# DisplaySupplies.net
KiCad netlist of a schematic drawn in Altium Designer
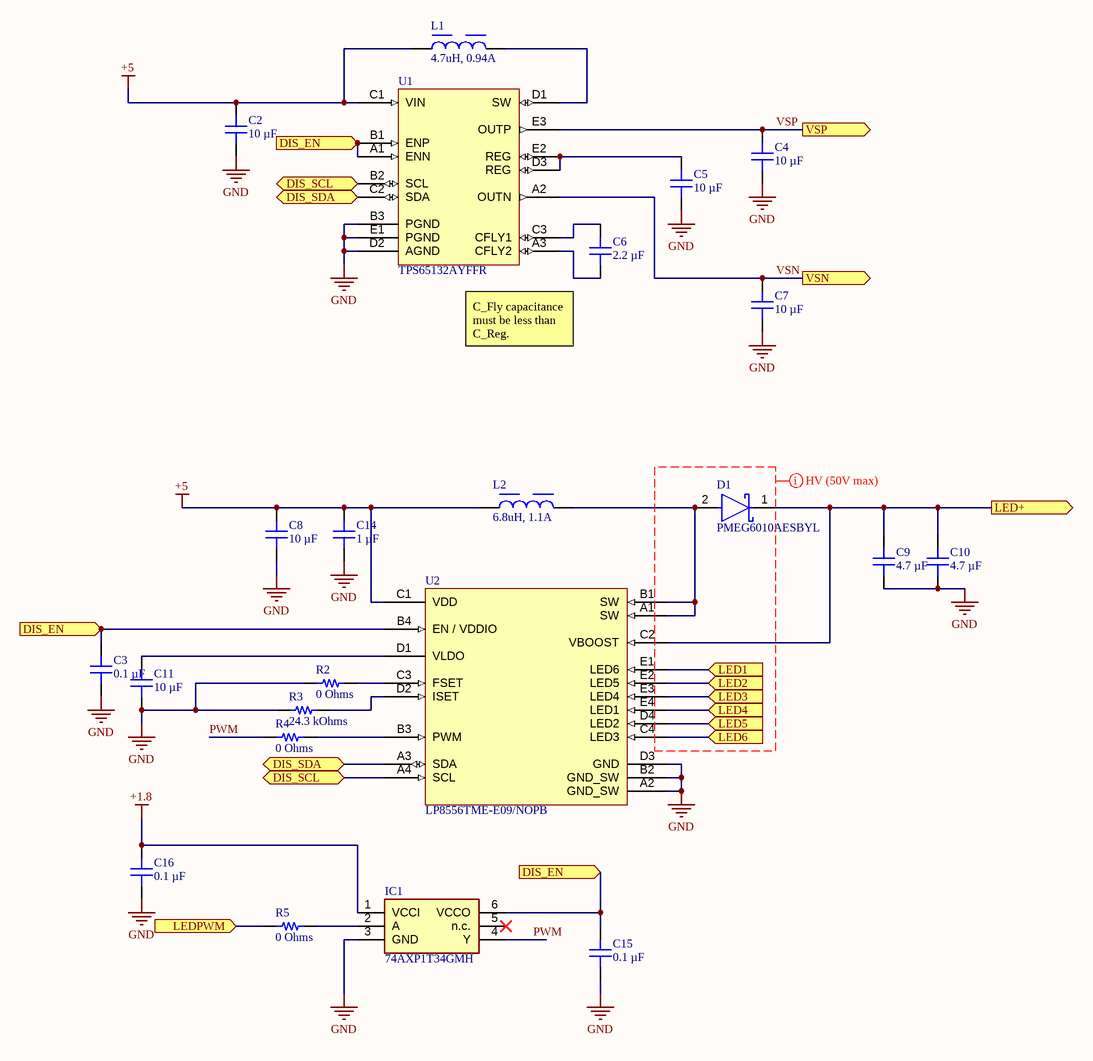
[diagram p0: DisplaySupplies.SchDoc]

(export (version "E")
  (design (tool "Eeschema 10.0.6"))
  (components
    (comp (ref "C2")
      (value "10 µF")
      (footprint "CAP 0603_1608")
      (description "CAP CER 10UF 16V X5R 0603")
      (fields
        (field (name "PART NUMBER") "GRM188R61C106MA73D")
        (field (name "MANUFACTURER") "Murata Electronics")
      )
      (libsource (lib "Celestial Altium Library - altium_library") (part "Capacitor"))
    )
    (comp (ref "C3")
      (value "0.1 µF")
      (footprint "CAP 0201_0603")
      (description "CAP CER 0.1UF 10V X5R 0201")
      (fields
        (field (name "PART NUMBER") "GRM033R61A104KE15D")
        (field (name "MANUFACTURER") "Murata Electronics")
      )
      (libsource (lib "Celestial Altium Library - altium_library") (part "Capacitor"))
    )
    (comp (ref "C4")
      (value "10 µF")
      (footprint "CAP 0603_1608")
      (description "CAP CER 10UF 16V X5R 0603")
      (fields
        (field (name "PART NUMBER") "GRM188R61C106MA73D")
        (field (name "MANUFACTURER") "Murata Electronics")
      )
      (libsource (lib "Celestial Altium Library - altium_library") (part "Capacitor"))
    )
    (comp (ref "C5")
      (value "10 µF")
      (footprint "CAP 0603_1608")
      (description "CAP CER 10UF 16V X5R 0603")
      (fields
        (field (name "PART NUMBER") "GRM188R61C106MA73D")
        (field (name "MANUFACTURER") "Murata Electronics")
      )
      (libsource (lib "Celestial Altium Library - altium_library") (part "Capacitor"))
    )
    (comp (ref "C6")
      (value "2.2 µF")
      (footprint "CAP 0402_1005")
      (description "CAP CER 2.2UF 16V X5R 0402")
      (fields
        (field (name "PART NUMBER") "GRM155R61C225ME44D")
        (field (name "MANUFACTURER") "Murata Electronics")
      )
      (libsource (lib "Celestial Altium Library - altium_library") (part "Capacitor"))
    )
    (comp (ref "C7")
      (value "10 µF")
      (footprint "CAP 0603_1608")
      (description "CAP CER 10UF 16V X5R 0603")
      (fields
        (field (name "PART NUMBER") "GRM188R61C106MA73D")
        (field (name "MANUFACTURER") "Murata Electronics")
      )
      (libsource (lib "Celestial Altium Library - altium_library") (part "Capacitor"))
    )
    (comp (ref "C8")
      (value "10 µF")
      (footprint "CAP 0603_1608")
      (description "CAP CER 10UF 16V X5R 0603")
      (fields
        (field (name "PART NUMBER") "GRM188R61C106MA73D")
        (field (name "MANUFACTURER") "Murata Electronics")
      )
      (libsource (lib "Celestial Altium Library - altium_library") (part "Capacitor"))
    )
    (comp (ref "C9")
      (value "4.7 µF")
      (footprint "CAP 1206_3216 - 0.8MM")
      (description "CAP CER 4.7UF 50V X7R 1206")
      (fields
        (field (name "PART NUMBER") "GRM31CR71H475KA12L")
        (field (name "MANUFACTURER") "Murata Electronics")
      )
      (libsource (lib "Celestial Altium Library - altium_library") (part "Capacitor"))
    )
    (comp (ref "C10")
      (value "4.7 µF")
      (footprint "CAP 1206_3216 - 0.8MM")
      (description "CAP CER 4.7UF 50V X7R 1206")
      (fields
        (field (name "PART NUMBER") "GRM31CR71H475KA12L")
        (field (name "MANUFACTURER") "Murata Electronics")
      )
      (libsource (lib "Celestial Altium Library - altium_library") (part "Capacitor"))
    )
    (comp (ref "C11")
      (value "10 µF")
      (footprint "CAP 0603_1608")
      (description "CAP CER 10UF 16V X5R 0603")
      (fields
        (field (name "PART NUMBER") "GRM188R61C106MA73D")
        (field (name "MANUFACTURER") "Murata Electronics")
      )
      (libsource (lib "Celestial Altium Library - altium_library") (part "Capacitor"))
    )
    (comp (ref "C14")
      (value "1 µF")
      (footprint "CAP 0402_1005")
      (description "CAP CER 1UF 16V X5R 0402")
      (fields
        (field (name "PART NUMBER") "GRM155R61C105MA12D")
        (field (name "MANUFACTURER") "Murata Electronics")
      )
      (libsource (lib "Celestial Altium Library - altium_library") (part "Capacitor"))
    )
    (comp (ref "C15")
      (value "0.1 µF")
      (footprint "CAP 0201_0603")
      (description "CAP CER 0.1UF 10V X5R 0201")
      (fields
        (field (name "PART NUMBER") "GRM033R61A104KE15D")
        (field (name "MANUFACTURER") "Murata Electronics")
      )
      (libsource (lib "Celestial Altium Library - altium_library") (part "Capacitor"))
    )
    (comp (ref "C16")
      (value "0.1 µF")
      (footprint "CAP 0201_0603")
      (description "CAP CER 0.1UF 10V X5R 0201")
      (fields
        (field (name "PART NUMBER") "GRM033R61A104KE15D")
        (field (name "MANUFACTURER") "Murata Electronics")
      )
      (libsource (lib "Celestial Altium Library - altium_library") (part "Capacitor"))
    )
    (comp (ref "D1")
      (value "PMEG6010AESBYL")
      (footprint "FP-SOD993-MFG")
      (description "DIODE SCHOTTKY 60V 1A DSN1006-2")
      (libsource (lib "Altium Content Vault") (part "fefb30dabb5d097ae2f038500735429"))
    )
    (comp (ref "IC1")
      (value "74AXP1T34GMH")
      (footprint "SamacSys:PESD3V3L5UF115")
      (description "Integrated Circuit")
      (fields (field (name "MOUSER PART NUMBER") "771-74AXP1T34GMH"))
      (libsource (lib "*") (part "74AXP1T34GMH"))
    )
    (comp (ref "L1")
      (value "4.7uH, 0.94A")
      (footprint "WE-MAPI_2510")
      (description "WE-MAPI SMT Power Inductor, size 2510, 4.7uH, 0.94A")
      (fields
        (field (name "MANUFACTURER") "Wurth Elektronik")
        (field (name "MANUFACTURER PART NUMBER") "74438323047")
      )
      (libsource (lib "WE-MAPI (rev22a)") (part "74438323047"))
    )
    (comp (ref "L2")
      (value "6.8uH, 1.1A")
      (footprint "WE-MAPI_3015")
      (description "WE-MAPI SMT Power Inductor, size 3015, 6.8uH, 1.1A")
      (fields
        (field (name "MANUFACTURER") "Wurth Elektronik")
        (field (name "MANUFACTURER PART NUMBER") "74438335068")
      )
      (libsource (lib "WE-MAPI (rev22a)") (part "74438335068"))
    )
    (comp (ref "R2")
      (value "0 Ohms")
      (footprint "RES 0402_1005")
      (description "RES SMD 0 OHM JUMPER 1/5W 0402")
      (fields (field (name "PART NUMBER") "CRCW04020000Z0EDHP") (field (name "MANUFACTURER") "Vishay Dale"))
      (libsource (lib "Celestial Altium Library - altium_library") (part "Resistor"))
    )
    (comp (ref "R3")
      (value "24.3 kOhms")
      (footprint "RES 0402_1005")
      (description "RES 24.3K OHM 1% 1/16W 0402")
      (fields (field (name "PART NUMBER") "RC0402FR-0724K3L") (field (name "MANUFACTURER") "Yageo"))
      (libsource (lib "Celestial Altium Library - altium_library") (part "Resistor"))
    )
    (comp (ref "R4")
      (value "0 Ohms")
      (footprint "RES 0402_1005")
      (description "RES SMD 0 OHM JUMPER 1/5W 0402")
      (fields (field (name "PART NUMBER") "CRCW04020000Z0EDHP") (field (name "MANUFACTURER") "Vishay Dale"))
      (libsource (lib "Celestial Altium Library - altium_library") (part "Resistor"))
    )
    (comp (ref "R5")
      (value "0 Ohms")
      (footprint "RES 0402_1005")
      (description "RES SMD 0 OHM JUMPER 1/5W 0402")
      (fields (field (name "PART NUMBER") "CRCW04020000Z0EDHP") (field (name "MANUFACTURER") "Vishay Dale"))
      (libsource (lib "Celestial Altium Library - altium_library") (part "Resistor"))
    )
    (comp (ref "U1")
      (value "TPS65132AYFFR")
      (footprint "BGA15C40P3X5_151X211X62")
      (libsource (lib "SimulaVR") (part "TPS65132AYFFR-Symbol-1"))
    )
    (comp (ref "U2")
      (value "LP8556TME-E09/NOPB")
      (footprint "BGA20C40P4X5_171X237X68")
      (description "6 channel high-efficiency/Efficacy LED backlight driver 20-DSBGA -30 to 85")
      (libsource (lib "SimulaVR") (part "LP8556TME-E09_NOPB-Symbol-1"))
    )
  )
  (nets
    (net (code "1") (name "+1.8") (class "Default")
      (node (ref "C16") (pin "2") (pinfunction "2_2") (pintype "passive"))
      (node (ref "IC1") (pin "1") (pinfunction "VCCI_1") (pintype "passive"))
    )
    (net (code "2") (name "+5") (class "Default")
      (node (ref "C14") (pin "2") (pinfunction "2_2") (pintype "passive"))
      (node (ref "C2") (pin "2") (pinfunction "2_2") (pintype "passive"))
      (node (ref "C8") (pin "2") (pinfunction "2_2") (pintype "passive"))
      (node (ref "L1") (pin "1") (pinfunction "1_1") (pintype "passive"))
      (node (ref "L2") (pin "1") (pinfunction "1_1") (pintype "passive"))
      (node (ref "U1") (pin "C1") (pinfunction "VIN_C1") (pintype "input"))
      (node (ref "U2") (pin "C1") (pinfunction "VDD_C1") (pintype "power_in"))
    )
    (net (code "3") (name "/DIS_EN") (class "Default")
      (node (ref "C15") (pin "2") (pinfunction "2_2") (pintype "passive"))
      (node (ref "C3") (pin "2") (pinfunction "2_2") (pintype "passive"))
      (node (ref "IC1") (pin "6") (pinfunction "VCCO_6") (pintype "passive"))
      (node (ref "U1") (pin "A1") (pinfunction "ENN_A1") (pintype "input"))
      (node (ref "U1") (pin "B1") (pinfunction "ENP_B1") (pintype "input"))
      (node (ref "U2") (pin "B4") (pinfunction "EN_/_VDDIO_B4") (pintype "input"))
    )
    (net (code "4") (name "/DIS_SCL") (class "Default")
      (node (ref "U1") (pin "B2") (pinfunction "SCL_B2") (pintype "bidirectional"))
      (node (ref "U2") (pin "A4") (pinfunction "SCL_A4") (pintype "input"))
    )
    (net (code "5") (name "/DIS_SDA") (class "Default")
      (node (ref "U1") (pin "C2") (pinfunction "SDA_C2") (pintype "bidirectional"))
      (node (ref "U2") (pin "A3") (pinfunction "SDA_A3") (pintype "bidirectional"))
    )
    (net (code "6") (name "/LED+") (class "Default")
      (node (ref "C10") (pin "2") (pinfunction "2_2") (pintype "passive"))
      (node (ref "C9") (pin "2") (pinfunction "2_2") (pintype "passive"))
      (node (ref "D1") (pin "1") (pinfunction "K_1") (pintype "passive"))
      (node (ref "U2") (pin "C2") (pinfunction "VBOOST_C2") (pintype "input"))
    )
    (net (code "7") (name "/LED1") (class "Default")
      (node (ref "U2") (pin "E1") (pinfunction "LED6_E1") (pintype "input"))
    )
    (net (code "8") (name "/LED2") (class "Default")
      (node (ref "U2") (pin "E2") (pinfunction "LED5_E2") (pintype "input"))
    )
    (net (code "9") (name "/LED3") (class "Default")
      (node (ref "U2") (pin "E3") (pinfunction "LED4_E3") (pintype "input"))
    )
    (net (code "10") (name "/LED4") (class "Default")
      (node (ref "U2") (pin "E4") (pinfunction "LED1_E4") (pintype "input"))
    )
    (net (code "11") (name "/LED5") (class "Default")
      (node (ref "U2") (pin "D4") (pinfunction "LED2_D4") (pintype "input"))
    )
    (net (code "12") (name "/LED6") (class "Default")
      (node (ref "U2") (pin "C4") (pinfunction "LED3_C4") (pintype "input"))
    )
    (net (code "13") (name "/LEDPWM") (class "Default")
      (node (ref "R5") (pin "2") (pinfunction "2_2") (pintype "passive"))
    )
    (net (code "14") (name "/PWM") (class "Default")
      (node (ref "IC1") (pin "4") (pinfunction "Y_4") (pintype "passive"))
      (node (ref "R4") (pin "2") (pinfunction "2_2") (pintype "passive"))
    )
    (net (code "15") (name "/VSN") (class "Default")
      (node (ref "C7") (pin "2") (pinfunction "2_2") (pintype "passive"))
      (node (ref "U1") (pin "A2") (pinfunction "OUTN_A2") (pintype "output"))
    )
    (net (code "16") (name "/VSP") (class "Default")
      (node (ref "C4") (pin "2") (pinfunction "2_2") (pintype "passive"))
      (node (ref "U1") (pin "E3") (pinfunction "OUTP_E3") (pintype "output"))
    )
    (net (code "17") (name "GND") (class "Default")
      (node (ref "C10") (pin "1") (pinfunction "1_1") (pintype "passive"))
      (node (ref "C11") (pin "1") (pinfunction "1_1") (pintype "passive"))
      (node (ref "C14") (pin "1") (pinfunction "1_1") (pintype "passive"))
      (node (ref "C15") (pin "1") (pinfunction "1_1") (pintype "passive"))
      (node (ref "C16") (pin "1") (pinfunction "1_1") (pintype "passive"))
      (node (ref "C2") (pin "1") (pinfunction "1_1") (pintype "passive"))
      (node (ref "C3") (pin "1") (pinfunction "1_1") (pintype "passive"))
      (node (ref "C4") (pin "1") (pinfunction "1_1") (pintype "passive"))
      (node (ref "C5") (pin "1") (pinfunction "1_1") (pintype "passive"))
      (node (ref "C7") (pin "1") (pinfunction "1_1") (pintype "passive"))
      (node (ref "C8") (pin "1") (pinfunction "1_1") (pintype "passive"))
      (node (ref "C9") (pin "1") (pinfunction "1_1") (pintype "passive"))
      (node (ref "IC1") (pin "3") (pinfunction "GND_3") (pintype "passive"))
      (node (ref "R2") (pin "2") (pinfunction "2_2") (pintype "passive"))
      (node (ref "R3") (pin "2") (pinfunction "2_2") (pintype "passive"))
      (node (ref "U1") (pin "B3") (pinfunction "PGND_B3") (pintype "power_in"))
      (node (ref "U1") (pin "D2") (pinfunction "AGND_D2") (pintype "power_in"))
      (node (ref "U1") (pin "E1") (pinfunction "PGND_E1") (pintype "power_in"))
      (node (ref "U2") (pin "A2") (pinfunction "GND_SW_A2") (pintype "power_in"))
      (node (ref "U2") (pin "B2") (pinfunction "GND_SW_B2") (pintype "power_in"))
      (node (ref "U2") (pin "D3") (pinfunction "GND_D3") (pintype "power_in"))
    )
    (net (code "18") (name "Net-(C5-Pad2)") (class "Default")
      (node (ref "C5") (pin "2") (pinfunction "2_2") (pintype "passive"))
      (node (ref "U1") (pin "D3") (pinfunction "REG_D3") (pintype "bidirectional"))
      (node (ref "U1") (pin "E2") (pinfunction "REG_E2") (pintype "bidirectional"))
    )
    (net (code "19") (name "Net-(D1-A)") (class "Default")
      (node (ref "D1") (pin "2") (pinfunction "A_2") (pintype "passive"))
      (node (ref "L2") (pin "2") (pinfunction "2_2") (pintype "passive"))
      (node (ref "U2") (pin "A1") (pinfunction "SW_A1") (pintype "input"))
      (node (ref "U2") (pin "B1") (pinfunction "SW_B1") (pintype "input"))
    )
    (net (code "20") (name "Net-(IC1-A)") (class "Default")
      (node (ref "IC1") (pin "2") (pinfunction "A_2") (pintype "passive"))
      (node (ref "R5") (pin "1") (pinfunction "1_1") (pintype "passive"))
    )
    (net (code "21") (name "Net-(U1-CFLY1)") (class "Default")
      (node (ref "C6") (pin "2") (pinfunction "2_2") (pintype "passive"))
      (node (ref "U1") (pin "C3") (pinfunction "CFLY1_C3") (pintype "bidirectional"))
    )
    (net (code "22") (name "Net-(U1-CFLY2)") (class "Default")
      (node (ref "C6") (pin "1") (pinfunction "1_1") (pintype "passive"))
      (node (ref "U1") (pin "A3") (pinfunction "CFLY2_A3") (pintype "bidirectional"))
    )
    (net (code "23") (name "Net-(U1-SW)") (class "Default")
      (node (ref "L1") (pin "2") (pinfunction "2_2") (pintype "passive"))
      (node (ref "U1") (pin "D1") (pinfunction "SW_D1") (pintype "bidirectional"))
    )
    (net (code "24") (name "Net-(U2-FSET)") (class "Default")
      (node (ref "R2") (pin "1") (pinfunction "1_1") (pintype "passive"))
      (node (ref "U2") (pin "C3") (pinfunction "FSET_C3") (pintype "input"))
    )
    (net (code "25") (name "Net-(U2-ISET)") (class "Default")
      (node (ref "R3") (pin "1") (pinfunction "1_1") (pintype "passive"))
      (node (ref "U2") (pin "D2") (pinfunction "ISET_D2") (pintype "input"))
    )
    (net (code "26") (name "Net-(U2-PWM)") (class "Default")
      (node (ref "R4") (pin "1") (pinfunction "1_1") (pintype "passive"))
      (node (ref "U2") (pin "B3") (pinfunction "PWM_B3") (pintype "input"))
    )
    (net (code "27") (name "Net-(U2-VLDO)") (class "Default")
      (node (ref "C11") (pin "2") (pinfunction "2_2") (pintype "passive"))
      (node (ref "U2") (pin "D1") (pinfunction "VLDO_D1") (pintype "power_in"))
    )
    (net (code "28") (name "unconnected-(IC1-n.c.-Pad5)") (class "Default")
      (node (ref "IC1") (pin "5") (pinfunction "n.c._5") (pintype "passive+no_connect"))
    )
  )
)
